# hw2.net
KiCad netlist of a schematic drawn in EAGLE
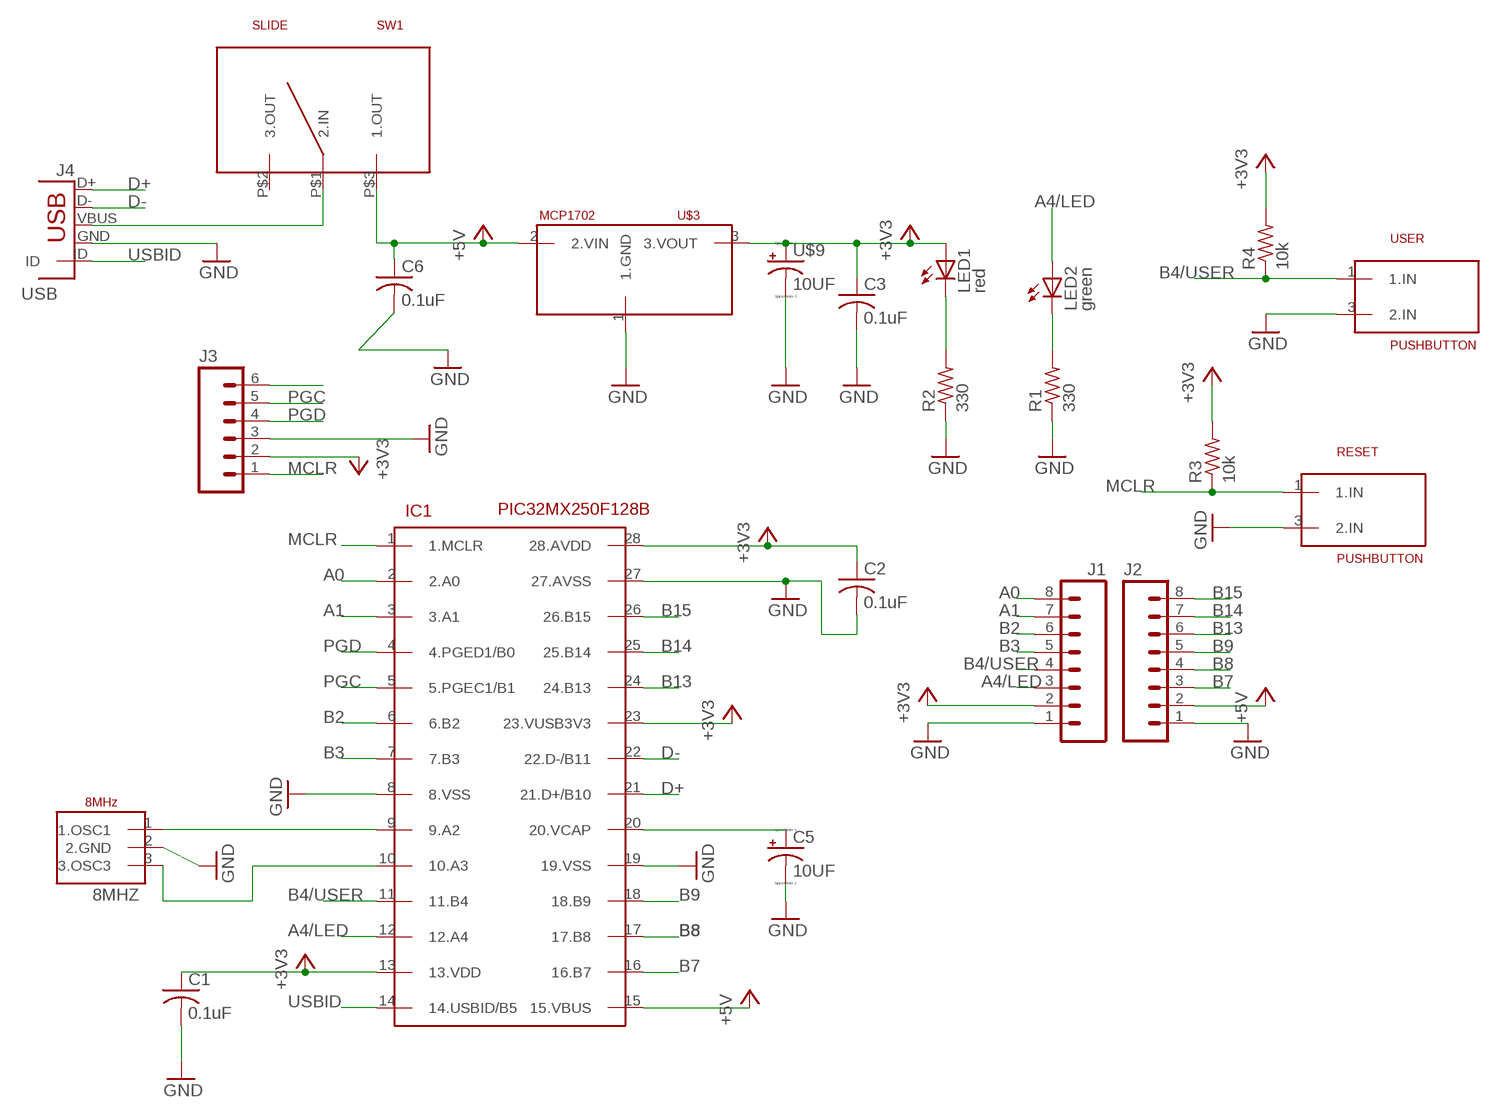
[diagram p0: schematic, sheet 1]

(export (version "E")
  (design (tool "Eeschema 10.0.6"))
  (components
    (comp (ref "C1")
      (value "0.1uF")
      (footprint "eagle-import:C025-025X050")
      (libsource (lib "eagle-import") (part "C-US025-025X050"))
    )
    (comp (ref "C2")
      (value "0.1uF")
      (footprint "eagle-import:C025-025X050")
      (libsource (lib "eagle-import") (part "C-US025-025X050"))
    )
    (comp (ref "C3")
      (value "0.1uF")
      (footprint "eagle-import:C025-025X050")
      (libsource (lib "eagle-import") (part "C-US025-025X050"))
    )
    (comp (ref "C5")
      (value "10UF")
      (footprint "eagle-import:TT2D4")
      (libsource (lib "eagle-import") (part "10UF"))
    )
    (comp (ref "C6")
      (value "0.1uF")
      (footprint "eagle-import:C025-025X050")
      (libsource (lib "eagle-import") (part "C-US025-025X050"))
    )
    (comp (ref "J1")
      (value "M08")
      (footprint "eagle-import:1X08_ROUND")
      (libsource (lib "eagle-import") (part "M08"))
    )
    (comp (ref "J2")
      (value "M08")
      (footprint "eagle-import:1X08_ROUND")
      (libsource (lib "eagle-import") (part "M08"))
    )
    (comp (ref "J3")
      (value "M06SILK_FEMALE_PTH")
      (footprint "eagle-import:1X06")
      (libsource (lib "eagle-import") (part "M06SILK_FEMALE_PTH"))
    )
    (comp (ref "J4")
      (value "USB")
      (footprint "eagle-import:USB-MB-H")
      (libsource (lib "eagle-import") (part "USB"))
    )
    (comp (ref "LED1")
      (value "red")
      (footprint "eagle-import:LED3MM")
      (libsource (lib "eagle-import") (part "LED3MM"))
    )
    (comp (ref "LED2")
      (value "green")
      (footprint "eagle-import:LED3MM")
      (libsource (lib "eagle-import") (part "LED3MM"))
    )
    (comp (ref "PIC")
      (value "PIC32MX250F128B")
      (footprint "eagle-import:DIL28-3")
      (libsource (lib "eagle-import") (part "PIC"))
    )
    (comp (ref "R1")
      (value "330")
      (footprint "eagle-import:0207_10")
      (libsource (lib "eagle-import") (part "R-US_0207/10"))
    )
    (comp (ref "R2")
      (value "330")
      (footprint "eagle-import:0207_10")
      (libsource (lib "eagle-import") (part "R-US_0207/10"))
    )
    (comp (ref "R3")
      (value "10k")
      (footprint "eagle-import:0207_10")
      (libsource (lib "eagle-import") (part "R-US_0207/10"))
    )
    (comp (ref "R4")
      (value "10k")
      (footprint "eagle-import:0207_10")
      (libsource (lib "eagle-import") (part "R-US_0207/10"))
    )
    (comp (ref "RESET")
      (value "PUSHBUTTON")
      (footprint "eagle-import:1X03")
      (libsource (lib "eagle-import") (part "PUSHBUTTON"))
    )
    (comp (ref "SLIDE")
      (value "SW1")
      (footprint "eagle-import:SLIDEWITCH")
      (libsource (lib "eagle-import") (part "SLIDE"))
    )
    (comp (ref "U$2")
      (value "8MHZ")
      (footprint "eagle-import:1X03")
      (libsource (lib "eagle-import") (part "8MHZ"))
    )
    (comp (ref "U$3")
      (value "MCP1702")
      (footprint "eagle-import:TO92")
      (libsource (lib "eagle-import") (part "MCP1702"))
    )
    (comp (ref "U$9")
      (value "10UF")
      (footprint "eagle-import:TT2D4")
      (libsource (lib "eagle-import") (part "10UF"))
    )
    (comp (ref "USER")
      (value "PUSHBUTTON")
      (footprint "eagle-import:1X03")
      (libsource (lib "eagle-import") (part "PUSHBUTTON"))
    )
  )
  (nets
    (net (code "1") (name "+3V3") (class "Default")
      (node (ref "C1") (pin "1") (pinfunction "1_1") (pintype "passive"))
      (node (ref "C2") (pin "1") (pinfunction "1_1") (pintype "passive"))
      (node (ref "C3") (pin "1") (pinfunction "1_1") (pintype "passive"))
      (node (ref "J1") (pin "2") (pinfunction "2_2") (pintype "passive"))
      (node (ref "J3") (pin "2") (pinfunction "2_2") (pintype "passive"))
      (node (ref "LED1") (pin "A") (pinfunction "A_A") (pintype "passive"))
      (node (ref "PIC") (pin "13") (pinfunction "13.VDD_13") (pintype "bidirectional"))
      (node (ref "PIC") (pin "23") (pinfunction "23.VUSB3V3_23") (pintype "bidirectional"))
      (node (ref "PIC") (pin "28") (pinfunction "28.AVDD_28") (pintype "bidirectional"))
      (node (ref "R3") (pin "2") (pinfunction "2_2") (pintype "passive"))
      (node (ref "R4") (pin "2") (pinfunction "2_2") (pintype "passive"))
      (node (ref "U$3") (pin "3") (pinfunction "3.VOUT_3") (pintype "bidirectional"))
      (node (ref "U$9") (pin "+") (pinfunction "+_+") (pintype "passive"))
    )
    (net (code "2") (name "+5V") (class "Default")
      (node (ref "C6") (pin "1") (pinfunction "1_1") (pintype "passive"))
      (node (ref "J2") (pin "2") (pinfunction "2_2") (pintype "passive"))
      (node (ref "PIC") (pin "15") (pinfunction "15.VBUS_15") (pintype "bidirectional"))
      (node (ref "SLIDE") (pin "P$3") (pinfunction "1.OUT_P$3") (pintype "bidirectional"))
      (node (ref "U$3") (pin "2") (pinfunction "2.VIN_2") (pintype "bidirectional"))
    )
    (net (code "3") (name "/A0") (class "Default")
      (node (ref "J1") (pin "8") (pinfunction "8_8") (pintype "passive"))
      (node (ref "PIC") (pin "2") (pinfunction "2.A0_2") (pintype "bidirectional"))
    )
    (net (code "4") (name "/A1") (class "Default")
      (node (ref "J1") (pin "7") (pinfunction "7_7") (pintype "passive"))
      (node (ref "PIC") (pin "3") (pinfunction "3.A1_3") (pintype "bidirectional"))
    )
    (net (code "5") (name "/A4{slash}LED") (class "Default")
      (node (ref "J1") (pin "3") (pinfunction "3_3") (pintype "passive"))
      (node (ref "LED2") (pin "A") (pinfunction "A_A") (pintype "passive"))
      (node (ref "PIC") (pin "12") (pinfunction "12.A4_12") (pintype "bidirectional"))
    )
    (net (code "6") (name "/B2") (class "Default")
      (node (ref "J1") (pin "6") (pinfunction "6_6") (pintype "passive"))
      (node (ref "PIC") (pin "6") (pinfunction "6.B2_6") (pintype "bidirectional"))
    )
    (net (code "7") (name "/B3") (class "Default")
      (node (ref "J1") (pin "5") (pinfunction "5_5") (pintype "passive"))
      (node (ref "PIC") (pin "7") (pinfunction "7.B3_7") (pintype "bidirectional"))
    )
    (net (code "8") (name "/B4{slash}USER") (class "Default")
      (node (ref "J1") (pin "4") (pinfunction "4_4") (pintype "passive"))
      (node (ref "PIC") (pin "11") (pinfunction "11.B4_11") (pintype "bidirectional"))
      (node (ref "R4") (pin "1") (pinfunction "1_1") (pintype "passive"))
      (node (ref "USER") (pin "1") (pinfunction "1.IN_1") (pintype "bidirectional"))
    )
    (net (code "9") (name "/B7") (class "Default")
      (node (ref "J2") (pin "3") (pinfunction "3_3") (pintype "passive"))
      (node (ref "PIC") (pin "16") (pinfunction "16.B7_16") (pintype "bidirectional"))
    )
    (net (code "10") (name "/B8") (class "Default")
      (node (ref "J2") (pin "4") (pinfunction "4_4") (pintype "passive"))
      (node (ref "PIC") (pin "17") (pinfunction "17.B8_17") (pintype "bidirectional"))
    )
    (net (code "11") (name "/B9") (class "Default")
      (node (ref "J2") (pin "5") (pinfunction "5_5") (pintype "passive"))
      (node (ref "PIC") (pin "18") (pinfunction "18.B9_18") (pintype "bidirectional"))
    )
    (net (code "12") (name "/B13") (class "Default")
      (node (ref "J2") (pin "6") (pinfunction "6_6") (pintype "passive"))
      (node (ref "PIC") (pin "24") (pinfunction "24.B13_24") (pintype "bidirectional"))
    )
    (net (code "13") (name "/B14") (class "Default")
      (node (ref "J2") (pin "7") (pinfunction "7_7") (pintype "passive"))
      (node (ref "PIC") (pin "25") (pinfunction "25.B14_25") (pintype "bidirectional"))
    )
    (net (code "14") (name "/B15") (class "Default")
      (node (ref "J2") (pin "8") (pinfunction "8_8") (pintype "passive"))
      (node (ref "PIC") (pin "26") (pinfunction "26.B15_26") (pintype "bidirectional"))
    )
    (net (code "15") (name "/D+") (class "Default")
      (node (ref "J4") (pin "D+") (pinfunction "D+_D+") (pintype "bidirectional"))
      (node (ref "PIC") (pin "21") (pinfunction "21.D+/B10_21") (pintype "bidirectional"))
    )
    (net (code "16") (name "/D-") (class "Default")
      (node (ref "J4") (pin "D-") (pinfunction "D-_D-") (pintype "bidirectional"))
      (node (ref "PIC") (pin "22") (pinfunction "22.D-/B11_22") (pintype "bidirectional"))
    )
    (net (code "17") (name "/MCLR") (class "Default")
      (node (ref "J3") (pin "1") (pinfunction "1_1") (pintype "passive"))
      (node (ref "PIC") (pin "1") (pinfunction "1.MCLR_1") (pintype "bidirectional"))
      (node (ref "R3") (pin "1") (pinfunction "1_1") (pintype "passive"))
      (node (ref "RESET") (pin "1") (pinfunction "1.IN_1") (pintype "bidirectional"))
    )
    (net (code "18") (name "/PGC") (class "Default")
      (node (ref "J3") (pin "5") (pinfunction "5_5") (pintype "passive"))
      (node (ref "PIC") (pin "5") (pinfunction "5.PGEC1/B1_5") (pintype "bidirectional"))
    )
    (net (code "19") (name "/PGD") (class "Default")
      (node (ref "J3") (pin "4") (pinfunction "4_4") (pintype "passive"))
      (node (ref "PIC") (pin "4") (pinfunction "4.PGED1/B0_4") (pintype "bidirectional"))
    )
    (net (code "20") (name "/USBID") (class "Default")
      (node (ref "J4") (pin "ID") (pinfunction "ID_ID") (pintype "bidirectional"))
      (node (ref "PIC") (pin "14") (pinfunction "14.USBID/B5_14") (pintype "bidirectional"))
    )
    (net (code "21") (name "GND") (class "Default")
      (node (ref "C1") (pin "2") (pinfunction "2_2") (pintype "passive"))
      (node (ref "C2") (pin "2") (pinfunction "2_2") (pintype "passive"))
      (node (ref "C3") (pin "2") (pinfunction "2_2") (pintype "passive"))
      (node (ref "C5") (pin "-") (pinfunction "-_-") (pintype "passive"))
      (node (ref "C6") (pin "2") (pinfunction "2_2") (pintype "passive"))
      (node (ref "J1") (pin "1") (pinfunction "1_1") (pintype "passive"))
      (node (ref "J2") (pin "1") (pinfunction "1_1") (pintype "passive"))
      (node (ref "J3") (pin "3") (pinfunction "3_3") (pintype "passive"))
      (node (ref "J4") (pin "GND") (pinfunction "GND_GND") (pintype "bidirectional"))
      (node (ref "PIC") (pin "19") (pinfunction "19.VSS_19") (pintype "bidirectional"))
      (node (ref "PIC") (pin "27") (pinfunction "27.AVSS_27") (pintype "bidirectional"))
      (node (ref "PIC") (pin "8") (pinfunction "8.VSS_8") (pintype "bidirectional"))
      (node (ref "R1") (pin "1") (pinfunction "1_1") (pintype "passive"))
      (node (ref "R2") (pin "1") (pinfunction "1_1") (pintype "passive"))
      (node (ref "RESET") (pin "3") (pinfunction "2.IN_3") (pintype "bidirectional"))
      (node (ref "U$2") (pin "2") (pinfunction "2.GND_2") (pintype "bidirectional"))
      (node (ref "U$3") (pin "1") (pinfunction "1.GND_1") (pintype "bidirectional"))
      (node (ref "U$9") (pin "-") (pinfunction "-_-") (pintype "passive"))
      (node (ref "USER") (pin "3") (pinfunction "2.IN_3") (pintype "bidirectional"))
    )
    (net (code "22") (name "Net-(LED1-C)") (class "Default")
      (node (ref "LED1") (pin "K") (pinfunction "C_K") (pintype "passive"))
      (node (ref "R2") (pin "2") (pinfunction "2_2") (pintype "passive"))
    )
    (net (code "23") (name "Net-(LED2-C)") (class "Default")
      (node (ref "LED2") (pin "K") (pinfunction "C_K") (pintype "passive"))
      (node (ref "R1") (pin "2") (pinfunction "2_2") (pintype "passive"))
    )
    (net (code "24") (name "Net-(PIC-9.A2)") (class "Default")
      (node (ref "PIC") (pin "9") (pinfunction "9.A2_9") (pintype "bidirectional"))
      (node (ref "U$2") (pin "1") (pinfunction "1.OSC1_1") (pintype "bidirectional"))
    )
    (net (code "25") (name "Net-(PIC-10.A3)") (class "Default")
      (node (ref "PIC") (pin "10") (pinfunction "10.A3_10") (pintype "bidirectional"))
      (node (ref "U$2") (pin "3") (pinfunction "3.OSC3_3") (pintype "bidirectional"))
    )
    (net (code "26") (name "Net-(PIC-20.VCAP)") (class "Default")
      (node (ref "C5") (pin "+") (pinfunction "+_+") (pintype "passive"))
      (node (ref "PIC") (pin "20") (pinfunction "20.VCAP_20") (pintype "bidirectional"))
    )
    (net (code "27") (name "Net-(SLIDE-2.IN)") (class "Default")
      (node (ref "J4") (pin "VBUS") (pinfunction "VBUS_VBUS") (pintype "bidirectional"))
      (node (ref "SLIDE") (pin "P$1") (pinfunction "2.IN_P$1") (pintype "bidirectional"))
    )
    (net (code "28") (name "unconnected-(J3-Pad6)") (class "Default")
      (node (ref "J3") (pin "6") (pinfunction "6_6") (pintype "passive"))
    )
    (net (code "29") (name "unconnected-(SLIDE-3.OUT-PadP$2)") (class "Default")
      (node (ref "SLIDE") (pin "P$2") (pinfunction "3.OUT_P$2") (pintype "bidirectional"))
    )
  )
)
